# module_ir.net
KiCad netlist of a schematic drawn in Altium Designer
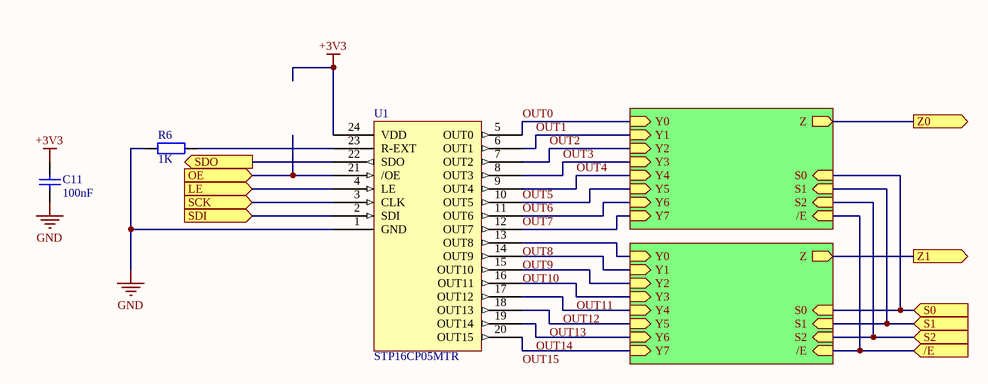
[diagram p0: module_ir.SchDoc]

(export (version "E")
  (design (tool "Eeschema 10.0.6"))
  (components
    (comp (ref "C11")
      (value "100nF")
      (footprint "FP_0805_CAP_085")
      (description "Capacitor")
      (fields (field (name "VOLTAGE") "50V"))
      (libsource (lib "hallglib-2018") (part "CAP 100nF"))
    )
    (comp (ref "R6")
      (value "1K")
      (footprint "FP_0805_RES")
      (description "Resistor")
      (fields (field (name "Comment") "R_EI"))
      (libsource (lib "hallglib") (part "RES"))
    )
    (comp (ref "U1")
      (value "STP16CP05MTR")
      (footprint "SOP24")
      (description "LED driver [16]")
      (libsource (lib "mb") (part "STP16CP05MTR"))
    )
  )
  (nets
    (net (code "1") (name "+3V3") (class "Default")
      (node (ref "C11") (pin "2") (pinfunction "2_2") (pintype "passive"))
      (node (ref "U1") (pin "24") (pinfunction "VDD_24") (pintype "passive"))
    )
    (net (code "2") (name "/LE") (class "Default")
      (node (ref "U1") (pin "4") (pinfunction "LE_4") (pintype "input"))
    )
    (net (code "3") (name "/OE") (class "Default")
      (node (ref "U1") (pin "21") (pinfunction "/OE_21") (pintype "input"))
    )
    (net (code "4") (name "/OUT0") (class "Default")
      (node (ref "U1") (pin "5") (pinfunction "OUT0_5") (pintype "output"))
    )
    (net (code "5") (name "/OUT1") (class "Default")
      (node (ref "U1") (pin "6") (pinfunction "OUT1_6") (pintype "output"))
    )
    (net (code "6") (name "/OUT2") (class "Default")
      (node (ref "U1") (pin "7") (pinfunction "OUT2_7") (pintype "output"))
    )
    (net (code "7") (name "/OUT3") (class "Default")
      (node (ref "U1") (pin "8") (pinfunction "OUT3_8") (pintype "output"))
    )
    (net (code "8") (name "/OUT4") (class "Default")
      (node (ref "U1") (pin "9") (pinfunction "OUT4_9") (pintype "output"))
    )
    (net (code "9") (name "/OUT5") (class "Default")
      (node (ref "U1") (pin "10") (pinfunction "OUT5_10") (pintype "output"))
    )
    (net (code "10") (name "/OUT6") (class "Default")
      (node (ref "U1") (pin "11") (pinfunction "OUT6_11") (pintype "output"))
    )
    (net (code "11") (name "/OUT7") (class "Default")
      (node (ref "U1") (pin "12") (pinfunction "OUT7_12") (pintype "output"))
    )
    (net (code "12") (name "/OUT8") (class "Default")
      (node (ref "U1") (pin "13") (pinfunction "OUT8_13") (pintype "output"))
    )
    (net (code "13") (name "/OUT9") (class "Default")
      (node (ref "U1") (pin "14") (pinfunction "OUT9_14") (pintype "output"))
    )
    (net (code "14") (name "/OUT10") (class "Default")
      (node (ref "U1") (pin "15") (pinfunction "OUT10_15") (pintype "output"))
    )
    (net (code "15") (name "/OUT11") (class "Default")
      (node (ref "U1") (pin "16") (pinfunction "OUT11_16") (pintype "output"))
    )
    (net (code "16") (name "/OUT12") (class "Default")
      (node (ref "U1") (pin "17") (pinfunction "OUT12_17") (pintype "output"))
    )
    (net (code "17") (name "/OUT13") (class "Default")
      (node (ref "U1") (pin "18") (pinfunction "OUT13_18") (pintype "output"))
    )
    (net (code "18") (name "/OUT14") (class "Default")
      (node (ref "U1") (pin "19") (pinfunction "OUT14_19") (pintype "output"))
    )
    (net (code "19") (name "/OUT15") (class "Default")
      (node (ref "U1") (pin "20") (pinfunction "OUT15_20") (pintype "output"))
    )
    (net (code "23") (name "/SCK") (class "Default")
      (node (ref "U1") (pin "3") (pinfunction "CLK_3") (pintype "input"))
    )
    (net (code "24") (name "/SDI") (class "Default")
      (node (ref "U1") (pin "2") (pinfunction "SDI_2") (pintype "input"))
    )
    (net (code "25") (name "/SDO") (class "Default")
      (node (ref "U1") (pin "22") (pinfunction "SDO_22") (pintype "output"))
    )
    (net (code "29") (name "GND") (class "Default")
      (node (ref "C11") (pin "1") (pinfunction "1_1") (pintype "passive"))
      (node (ref "R6") (pin "2") (pinfunction "2_2") (pintype "passive"))
      (node (ref "U1") (pin "1") (pinfunction "GND_1") (pintype "power_in"))
    )
    (net (code "30") (name "Net-(U1-R-EXT)") (class "Default")
      (node (ref "R6") (pin "1") (pinfunction "1_1") (pintype "passive"))
      (node (ref "U1") (pin "23") (pinfunction "R-EXT_23") (pintype "passive"))
    )
  )
)
